# silnik.net
KiCad netlist of a schematic drawn in Altium Designer
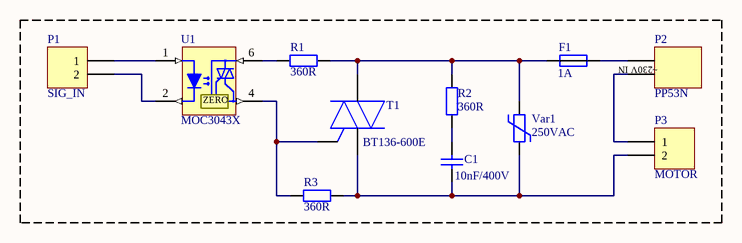
[diagram p0: silnik.SchDoc]

(export (version "E")
  (design (tool "Eeschema 10.0.6"))
  (components
    (comp (ref "C1")
      (value "10nF/400V")
      (footprint "10nF/310VAC")
      (description "Capacitor")
      (libsource (lib "Library") (part "Cap"))
    )
    (comp (ref "F1") (value "1A") (footprint "5x20mm") (libsource (lib "Library") (part "FUSE")))
    (comp (ref "P1") (value "SIG_IN") (footprint "PAD2_2.54mm") (libsource (lib "") (part "PAD2_1")))
    (comp (ref "P2")
      (value "PP53N")
      (footprint "PP53N")
      (description "Obudowa: do zasilacza; X:78,5mm; Y:40mm; Z:21mm")
      (libsource (lib "Connectors") (part "PP53N"))
    )
    (comp (ref "P3") (value "MOTOR") (footprint "PAD2_5mm") (libsource (lib "Connectors") (part "PAD2")))
    (comp (ref "R1")
      (value "360R")
      (footprint "RCL_0207/10")
      (description "Resistor")
      (libsource (lib "") (part "Res_1"))
    )
    (comp (ref "R2")
      (value "360R")
      (footprint "RCL_0207/10")
      (description "Resistor")
      (libsource (lib "Library") (part "Res"))
    )
    (comp (ref "R3")
      (value "360R")
      (footprint "RCL_0207/10")
      (description "Resistor")
      (libsource (lib "") (part "Res_1"))
    )
    (comp (ref "T1")
      (value "BT136-600E")
      (footprint "TO-220-H")
      (description "Triak; 600V; 4A; 11mA")
      (libsource (lib "Library") (part "BT136-600E"))
    )
    (comp (ref "U1") (value "MOC3043X") (footprint "DIP-6") (libsource (lib "Library") (part "MOC3043X")))
    (comp (ref "Var1")
      (value "250VAC")
      (footprint "HEL5D391K_5mm_var")
      (description "HEL5D391K")
      (libsource (lib "Library") (part "Varistor"))
    )
  )
  (nets
    (net (code "1") (name "Net-(C1-Pad1)") (class "Default")
      (node (ref "C1") (pin "1") (pinfunction "1_1") (pintype "passive"))
      (node (ref "R2") (pin "1") (pinfunction "1_1") (pintype "passive"))
    )
    (net (code "2") (name "Net-(F1-Pad2)") (class "Default")
      (node (ref "F1") (pin "2") (pinfunction "2_2") (pintype "passive"))
      (node (ref "P2") (pin "2") (pinfunction "2_2") (pintype "passive"))
    )
    (net (code "3") (name "Net-(P1-Pad1)") (class "Default")
      (node (ref "P1") (pin "1") (pinfunction "1_1") (pintype "passive"))
      (node (ref "U1") (pin "1") (pinfunction "1_1") (pintype "input"))
    )
    (net (code "4") (name "Net-(P1-Pad2)") (class "Default")
      (node (ref "P1") (pin "2") (pinfunction "2_2") (pintype "passive"))
      (node (ref "U1") (pin "2") (pinfunction "2_2") (pintype "output"))
    )
    (net (code "5") (name "Net-(P2-Pad1)") (class "Default")
      (node (ref "P2") (pin "1") (pinfunction "1_1") (pintype "passive"))
      (node (ref "P3") (pin "1") (pinfunction "1_1") (pintype "passive"))
    )
    (net (code "6") (name "Net-(R1-Pad1)") (class "Default")
      (node (ref "R1") (pin "1") (pinfunction "1_1") (pintype "passive"))
      (node (ref "U1") (pin "6") (pinfunction "6_6") (pintype "input"))
    )
    (net (code "7") (name "Net-(T1-G)") (class "Default")
      (node (ref "R3") (pin "1") (pinfunction "1_1") (pintype "passive"))
      (node (ref "T1") (pin "3") (pinfunction "G_3") (pintype "passive"))
      (node (ref "U1") (pin "4") (pinfunction "4_4") (pintype "output"))
    )
    (net (code "8") (name "Net-(T1-T1)") (class "Default")
      (node (ref "C1") (pin "2") (pinfunction "2_2") (pintype "passive"))
      (node (ref "P3") (pin "2") (pinfunction "2_2") (pintype "passive"))
      (node (ref "R3") (pin "2") (pinfunction "2_2") (pintype "passive"))
      (node (ref "T1") (pin "1") (pinfunction "T1_1") (pintype "passive"))
      (node (ref "Var1") (pin "2") (pinfunction "2_2") (pintype "passive"))
    )
    (net (code "9") (name "Net-(T1-T2)") (class "Default")
      (node (ref "F1") (pin "1") (pinfunction "1_1") (pintype "passive"))
      (node (ref "R1") (pin "2") (pinfunction "2_2") (pintype "passive"))
      (node (ref "R2") (pin "2") (pinfunction "2_2") (pintype "passive"))
      (node (ref "T1") (pin "2") (pinfunction "T2_2") (pintype "passive"))
      (node (ref "Var1") (pin "1") (pinfunction "1_1") (pintype "passive"))
    )
  )
)
